# Connectors.net
KiCad netlist of a schematic drawn in Altium Designer
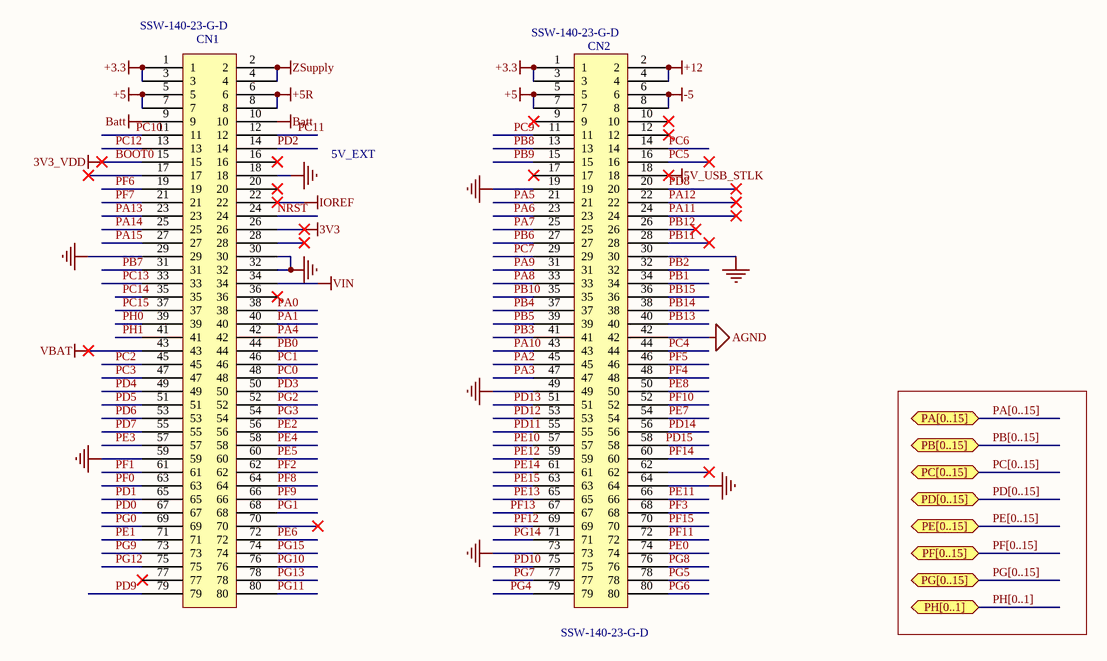
[diagram p0: Connectors.SchDoc]

(export (version "E")
  (design (tool "Eeschema 10.0.6"))
  (components
    (comp (ref "CN1")
      (value "SSW-140-23-G-D")
      (footprint "SSW-140-23-G-D")
      (description "80 Position Receptacle Connector Through Hole")
      (fields (field (name "SUPPLIER PART NUMBER 1") "SSW-140-23-G-D") (field (name "MANUFACTURER") "Samtec"))
      (libsource (lib "ZLS_Schematic_lib") (part "SSW-140-23-G-D"))
    )
    (comp (ref "CN2")
      (value "SSW-140-23-G-D")
      (footprint "SSW-140-23-G-D")
      (description "80 Position Receptacle Connector Through Hole")
      (fields (field (name "SUPPLIER PART NUMBER 1") "SSW-140-23-G-D") (field (name "MANUFACTURER") "Samtec"))
      (libsource (lib "ZLS_Schematic_lib") (part "SSW-140-23-G-D"))
    )
  )
  (nets
    (net (code "3") (name "+3.3") (class "Default")
      (node (ref "CN1") (pin "1") (pinfunction "1_1") (pintype "passive"))
      (node (ref "CN1") (pin "3") (pinfunction "3_3") (pintype "passive"))
      (node (ref "CN2") (pin "1") (pinfunction "1_1") (pintype "passive"))
      (node (ref "CN2") (pin "3") (pinfunction "3_3") (pintype "passive"))
    )
    (net (code "4") (name "+5") (class "Default")
      (node (ref "CN1") (pin "5") (pinfunction "5_5") (pintype "passive"))
      (node (ref "CN1") (pin "7") (pinfunction "7_7") (pintype "passive"))
      (node (ref "CN2") (pin "5") (pinfunction "5_5") (pintype "passive"))
      (node (ref "CN2") (pin "7") (pinfunction "7_7") (pintype "passive"))
    )
    (net (code "5") (name "+5R") (class "Default")
      (node (ref "CN1") (pin "6") (pinfunction "6_6") (pintype "passive"))
      (node (ref "CN1") (pin "8") (pinfunction "8_8") (pintype "passive"))
    )
    (net (code "6") (name "+12") (class "Default")
      (node (ref "CN2") (pin "2") (pinfunction "2_2") (pintype "passive"))
      (node (ref "CN2") (pin "4") (pinfunction "4_4") (pintype "passive"))
    )
    (net (code "7") (name "-5") (class "Default")
      (node (ref "CN2") (pin "6") (pinfunction "6_6") (pintype "passive"))
      (node (ref "CN2") (pin "8") (pinfunction "8_8") (pintype "passive"))
    )
    (net (code "8") (name "/NRST") (class "Default")
      (node (ref "CN1") (pin "24") (pinfunction "24_24") (pintype "passive"))
    )
    (net (code "9") (name "/PA0") (class "Default")
      (node (ref "CN1") (pin "38") (pinfunction "38_38") (pintype "passive"))
    )
    (net (code "10") (name "/PA1") (class "Default")
      (node (ref "CN1") (pin "40") (pinfunction "40_40") (pintype "passive"))
    )
    (net (code "11") (name "/PA2") (class "Default")
      (node (ref "CN2") (pin "45") (pinfunction "45_45") (pintype "passive"))
    )
    (net (code "12") (name "/PA3") (class "Default")
      (node (ref "CN2") (pin "47") (pinfunction "47_47") (pintype "passive"))
    )
    (net (code "13") (name "/PA4") (class "Default")
      (node (ref "CN1") (pin "42") (pinfunction "42_42") (pintype "passive"))
    )
    (net (code "14") (name "/PA5") (class "Default")
      (node (ref "CN2") (pin "21") (pinfunction "21_21") (pintype "passive"))
    )
    (net (code "15") (name "/PA6") (class "Default")
      (node (ref "CN2") (pin "23") (pinfunction "23_23") (pintype "passive"))
    )
    (net (code "16") (name "/PA7") (class "Default")
      (node (ref "CN2") (pin "25") (pinfunction "25_25") (pintype "passive"))
    )
    (net (code "17") (name "/PA8") (class "Default")
      (node (ref "CN2") (pin "33") (pinfunction "33_33") (pintype "passive"))
    )
    (net (code "18") (name "/PA9") (class "Default")
      (node (ref "CN2") (pin "31") (pinfunction "31_31") (pintype "passive"))
    )
    (net (code "19") (name "/PA10") (class "Default")
      (node (ref "CN2") (pin "43") (pinfunction "43_43") (pintype "passive"))
    )
    (net (code "20") (name "/PA11") (class "Default")
      (node (ref "CN2") (pin "24") (pinfunction "24_24") (pintype "passive+no_connect"))
    )
    (net (code "21") (name "/PA12") (class "Default")
      (node (ref "CN2") (pin "22") (pinfunction "22_22") (pintype "passive+no_connect"))
    )
    (net (code "22") (name "/PA13") (class "Default")
      (node (ref "CN1") (pin "23") (pinfunction "23_23") (pintype "passive"))
    )
    (net (code "23") (name "/PA14") (class "Default")
      (node (ref "CN1") (pin "25") (pinfunction "25_25") (pintype "passive"))
    )
    (net (code "24") (name "/PA15") (class "Default")
      (node (ref "CN1") (pin "27") (pinfunction "27_27") (pintype "passive"))
    )
    (net (code "26") (name "/PB0") (class "Default")
      (node (ref "CN1") (pin "44") (pinfunction "44_44") (pintype "passive"))
    )
    (net (code "27") (name "/PB1") (class "Default")
      (node (ref "CN2") (pin "34") (pinfunction "34_34") (pintype "passive"))
    )
    (net (code "28") (name "/PB2") (class "Default")
      (node (ref "CN2") (pin "32") (pinfunction "32_32") (pintype "passive"))
    )
    (net (code "29") (name "/PB3") (class "Default")
      (node (ref "CN2") (pin "41") (pinfunction "41_41") (pintype "passive"))
    )
    (net (code "30") (name "/PB4") (class "Default")
      (node (ref "CN2") (pin "37") (pinfunction "37_37") (pintype "passive"))
    )
    (net (code "31") (name "/PB5") (class "Default")
      (node (ref "CN2") (pin "39") (pinfunction "39_39") (pintype "passive"))
    )
    (net (code "32") (name "/PB6") (class "Default")
      (node (ref "CN2") (pin "27") (pinfunction "27_27") (pintype "passive"))
    )
    (net (code "33") (name "/PB7") (class "Default")
      (node (ref "CN1") (pin "31") (pinfunction "31_31") (pintype "passive"))
    )
    (net (code "34") (name "/PB8") (class "Default")
      (node (ref "CN2") (pin "13") (pinfunction "13_13") (pintype "passive"))
    )
    (net (code "35") (name "/PB9") (class "Default")
      (node (ref "CN2") (pin "15") (pinfunction "15_15") (pintype "passive"))
    )
    (net (code "36") (name "/PB10") (class "Default")
      (node (ref "CN2") (pin "35") (pinfunction "35_35") (pintype "passive"))
    )
    (net (code "37") (name "/PB11") (class "Default")
      (node (ref "CN2") (pin "28") (pinfunction "28_28") (pintype "passive+no_connect"))
    )
    (net (code "38") (name "/PB12") (class "Default")
      (node (ref "CN2") (pin "26") (pinfunction "26_26") (pintype "passive+no_connect"))
    )
    (net (code "39") (name "/PB13") (class "Default")
      (node (ref "CN2") (pin "40") (pinfunction "40_40") (pintype "passive"))
    )
    (net (code "40") (name "/PB14") (class "Default")
      (node (ref "CN2") (pin "38") (pinfunction "38_38") (pintype "passive"))
    )
    (net (code "41") (name "/PB15") (class "Default")
      (node (ref "CN2") (pin "36") (pinfunction "36_36") (pintype "passive"))
    )
    (net (code "43") (name "/PC0") (class "Default")
      (node (ref "CN1") (pin "48") (pinfunction "48_48") (pintype "passive"))
    )
    (net (code "44") (name "/PC1") (class "Default")
      (node (ref "CN1") (pin "46") (pinfunction "46_46") (pintype "passive"))
    )
    (net (code "45") (name "/PC2") (class "Default")
      (node (ref "CN1") (pin "45") (pinfunction "45_45") (pintype "passive"))
    )
    (net (code "46") (name "/PC3") (class "Default")
      (node (ref "CN1") (pin "47") (pinfunction "47_47") (pintype "passive"))
    )
    (net (code "47") (name "/PC4") (class "Default")
      (node (ref "CN2") (pin "44") (pinfunction "44_44") (pintype "passive"))
    )
    (net (code "48") (name "/PC5") (class "Default")
      (node (ref "CN2") (pin "16") (pinfunction "16_16") (pintype "passive+no_connect"))
    )
    (net (code "49") (name "/PC6") (class "Default")
      (node (ref "CN2") (pin "14") (pinfunction "14_14") (pintype "passive"))
    )
    (net (code "50") (name "/PC7") (class "Default")
      (node (ref "CN2") (pin "29") (pinfunction "29_29") (pintype "passive"))
    )
    (net (code "51") (name "/PC9") (class "Default")
      (node (ref "CN2") (pin "11") (pinfunction "11_11") (pintype "passive"))
    )
    (net (code "52") (name "/PC10") (class "Default")
      (node (ref "CN1") (pin "11") (pinfunction "11_11") (pintype "passive"))
    )
    (net (code "53") (name "/PC11") (class "Default")
      (node (ref "CN1") (pin "12") (pinfunction "12_12") (pintype "passive"))
    )
    (net (code "54") (name "/PC12") (class "Default")
      (node (ref "CN1") (pin "13") (pinfunction "13_13") (pintype "passive"))
    )
    (net (code "55") (name "/PC13") (class "Default")
      (node (ref "CN1") (pin "33") (pinfunction "33_33") (pintype "passive"))
    )
    (net (code "56") (name "/PC14") (class "Default")
      (node (ref "CN1") (pin "35") (pinfunction "35_35") (pintype "passive"))
    )
    (net (code "57") (name "/PC15") (class "Default")
      (node (ref "CN1") (pin "37") (pinfunction "37_37") (pintype "passive"))
    )
    (net (code "59") (name "/PD0") (class "Default")
      (node (ref "CN1") (pin "67") (pinfunction "67_67") (pintype "passive"))
    )
    (net (code "60") (name "/PD1") (class "Default")
      (node (ref "CN1") (pin "65") (pinfunction "65_65") (pintype "passive"))
    )
    (net (code "61") (name "/PD2") (class "Default")
      (node (ref "CN1") (pin "14") (pinfunction "14_14") (pintype "passive"))
    )
    (net (code "62") (name "/PD3") (class "Default")
      (node (ref "CN1") (pin "50") (pinfunction "50_50") (pintype "passive"))
    )
    (net (code "63") (name "/PD4") (class "Default")
      (node (ref "CN1") (pin "49") (pinfunction "49_49") (pintype "passive"))
    )
    (net (code "64") (name "/PD5") (class "Default")
      (node (ref "CN1") (pin "51") (pinfunction "51_51") (pintype "passive"))
    )
    (net (code "65") (name "/PD6") (class "Default")
      (node (ref "CN1") (pin "53") (pinfunction "53_53") (pintype "passive"))
    )
    (net (code "66") (name "/PD7") (class "Default")
      (node (ref "CN1") (pin "55") (pinfunction "55_55") (pintype "passive"))
    )
    (net (code "67") (name "/PD8") (class "Default")
      (node (ref "CN2") (pin "20") (pinfunction "20_20") (pintype "passive+no_connect"))
    )
    (net (code "68") (name "/PD9") (class "Default")
      (node (ref "CN1") (pin "79") (pinfunction "79_79") (pintype "passive"))
    )
    (net (code "69") (name "/PD10") (class "Default")
      (node (ref "CN2") (pin "75") (pinfunction "75_75") (pintype "passive"))
    )
    (net (code "70") (name "/PD11") (class "Default")
      (node (ref "CN2") (pin "55") (pinfunction "55_55") (pintype "passive"))
    )
    (net (code "71") (name "/PD12") (class "Default")
      (node (ref "CN2") (pin "53") (pinfunction "53_53") (pintype "passive"))
    )
    (net (code "72") (name "/PD13") (class "Default")
      (node (ref "CN2") (pin "51") (pinfunction "51_51") (pintype "passive"))
    )
    (net (code "73") (name "/PD14") (class "Default")
      (node (ref "CN2") (pin "56") (pinfunction "56_56") (pintype "passive"))
    )
    (net (code "76") (name "/PE0") (class "Default")
      (node (ref "CN2") (pin "74") (pinfunction "74_74") (pintype "passive"))
    )
    (net (code "77") (name "/PE1") (class "Default")
      (node (ref "CN1") (pin "71") (pinfunction "71_71") (pintype "passive"))
    )
    (net (code "78") (name "/PE2") (class "Default")
      (node (ref "CN1") (pin "56") (pinfunction "56_56") (pintype "passive"))
    )
    (net (code "79") (name "/PE3") (class "Default")
      (node (ref "CN1") (pin "57") (pinfunction "57_57") (pintype "passive"))
    )
    (net (code "80") (name "/PE4") (class "Default")
      (node (ref "CN1") (pin "58") (pinfunction "58_58") (pintype "passive"))
    )
    (net (code "81") (name "/PE5") (class "Default")
      (node (ref "CN1") (pin "60") (pinfunction "60_60") (pintype "passive"))
    )
    (net (code "82") (name "/PE6") (class "Default")
      (node (ref "CN1") (pin "72") (pinfunction "72_72") (pintype "passive"))
    )
    (net (code "83") (name "/PE7") (class "Default")
      (node (ref "CN2") (pin "54") (pinfunction "54_54") (pintype "passive"))
    )
    (net (code "84") (name "/PE8") (class "Default")
      (node (ref "CN2") (pin "50") (pinfunction "50_50") (pintype "passive"))
    )
    (net (code "85") (name "/PE10") (class "Default")
      (node (ref "CN2") (pin "57") (pinfunction "57_57") (pintype "passive"))
    )
    (net (code "86") (name "/PE11") (class "Default")
      (node (ref "CN2") (pin "66") (pinfunction "66_66") (pintype "passive"))
    )
    (net (code "87") (name "/PE12") (class "Default")
      (node (ref "CN2") (pin "59") (pinfunction "59_59") (pintype "passive"))
    )
    (net (code "88") (name "/PE13") (class "Default")
      (node (ref "CN2") (pin "65") (pinfunction "65_65") (pintype "passive"))
    )
    (net (code "89") (name "/PE14") (class "Default")
      (node (ref "CN2") (pin "61") (pinfunction "61_61") (pintype "passive"))
    )
    (net (code "90") (name "/PE15") (class "Default")
      (node (ref "CN2") (pin "63") (pinfunction "63_63") (pintype "passive"))
    )
    (net (code "92") (name "/PF0") (class "Default")
      (node (ref "CN1") (pin "63") (pinfunction "63_63") (pintype "passive"))
    )
    (net (code "93") (name "/PF1") (class "Default")
      (node (ref "CN1") (pin "61") (pinfunction "61_61") (pintype "passive"))
    )
    (net (code "94") (name "/PF2") (class "Default")
      (node (ref "CN1") (pin "62") (pinfunction "62_62") (pintype "passive"))
    )
    (net (code "95") (name "/PF3") (class "Default")
      (node (ref "CN2") (pin "68") (pinfunction "68_68") (pintype "passive"))
    )
    (net (code "96") (name "/PF4") (class "Default")
      (node (ref "CN2") (pin "48") (pinfunction "48_48") (pintype "passive"))
    )
    (net (code "97") (name "/PF5") (class "Default")
      (node (ref "CN2") (pin "46") (pinfunction "46_46") (pintype "passive"))
    )
    (net (code "98") (name "/PF6") (class "Default")
      (node (ref "CN1") (pin "19") (pinfunction "19_19") (pintype "passive"))
    )
    (net (code "99") (name "/PF7") (class "Default")
      (node (ref "CN1") (pin "21") (pinfunction "21_21") (pintype "passive"))
    )
    (net (code "100") (name "/PF8") (class "Default")
      (node (ref "CN1") (pin "64") (pinfunction "64_64") (pintype "passive"))
    )
    (net (code "101") (name "/PF9") (class "Default")
      (node (ref "CN1") (pin "66") (pinfunction "66_66") (pintype "passive"))
    )
    (net (code "102") (name "/PF10") (class "Default")
      (node (ref "CN2") (pin "52") (pinfunction "52_52") (pintype "passive"))
    )
    (net (code "103") (name "/PF11") (class "Default")
      (node (ref "CN2") (pin "72") (pinfunction "72_72") (pintype "passive"))
    )
    (net (code "104") (name "/PF12") (class "Default")
      (node (ref "CN2") (pin "69") (pinfunction "69_69") (pintype "passive"))
    )
    (net (code "105") (name "/PF13") (class "Default")
      (node (ref "CN2") (pin "67") (pinfunction "67_67") (pintype "passive"))
    )
    (net (code "106") (name "/PF14") (class "Default")
      (node (ref "CN2") (pin "60") (pinfunction "60_60") (pintype "passive"))
    )
    (net (code "107") (name "/PF15") (class "Default")
      (node (ref "CN2") (pin "70") (pinfunction "70_70") (pintype "passive"))
    )
    (net (code "109") (name "/PG0") (class "Default")
      (node (ref "CN1") (pin "69") (pinfunction "69_69") (pintype "passive"))
    )
    (net (code "110") (name "/PG1") (class "Default")
      (node (ref "CN1") (pin "68") (pinfunction "68_68") (pintype "passive"))
    )
    (net (code "111") (name "/PG2") (class "Default")
      (node (ref "CN1") (pin "52") (pinfunction "52_52") (pintype "passive"))
    )
    (net (code "112") (name "/PG3") (class "Default")
      (node (ref "CN1") (pin "54") (pinfunction "54_54") (pintype "passive"))
    )
    (net (code "113") (name "/PG4") (class "Default")
      (node (ref "CN2") (pin "79") (pinfunction "79_79") (pintype "passive"))
    )
    (net (code "114") (name "/PG5") (class "Default")
      (node (ref "CN2") (pin "78") (pinfunction "78_78") (pintype "passive"))
    )
    (net (code "115") (name "/PG6") (class "Default")
      (node (ref "CN2") (pin "80") (pinfunction "80_80") (pintype "passive"))
    )
    (net (code "116") (name "/PG7") (class "Default")
      (node (ref "CN2") (pin "77") (pinfunction "77_77") (pintype "passive"))
    )
    (net (code "117") (name "/PG8") (class "Default")
      (node (ref "CN2") (pin "76") (pinfunction "76_76") (pintype "passive"))
    )
    (net (code "118") (name "/PG9") (class "Default")
      (node (ref "CN1") (pin "73") (pinfunction "73_73") (pintype "passive"))
    )
    (net (code "119") (name "/PG10") (class "Default")
      (node (ref "CN1") (pin "76") (pinfunction "76_76") (pintype "passive"))
    )
    (net (code "120") (name "/PG11") (class "Default")
      (node (ref "CN1") (pin "80") (pinfunction "80_80") (pintype "passive"))
    )
    (net (code "121") (name "/PG12") (class "Default")
      (node (ref "CN1") (pin "75") (pinfunction "75_75") (pintype "passive"))
    )
    (net (code "122") (name "/PG13") (class "Default")
      (node (ref "CN1") (pin "78") (pinfunction "78_78") (pintype "passive"))
    )
    (net (code "123") (name "/PG14") (class "Default")
      (node (ref "CN2") (pin "71") (pinfunction "71_71") (pintype "passive"))
    )
    (net (code "124") (name "/PG15") (class "Default")
      (node (ref "CN1") (pin "74") (pinfunction "74_74") (pintype "passive"))
    )
    (net (code "126") (name "/PH0") (class "Default")
      (node (ref "CN1") (pin "39") (pinfunction "39_39") (pintype "passive"))
    )
    (net (code "127") (name "/PH1") (class "Default")
      (node (ref "CN1") (pin "41") (pinfunction "41_41") (pintype "passive"))
    )
    (net (code "129") (name "3V3") (class "Default")
      (node (ref "CN1") (pin "26") (pinfunction "26_26") (pintype "passive"))
    )
    (net (code "130") (name "3V3_VDD") (class "Default")
      (node (ref "CN1") (pin "15") (pinfunction "15_15") (pintype "passive"))
    )
    (net (code "131") (name "5V_USB_STLK") (class "Default")
      (node (ref "CN2") (pin "18") (pinfunction "18_18") (pintype "passive"))
    )
    (net (code "132") (name "AGND") (class "Default")
      (node (ref "CN2") (pin "42") (pinfunction "42_42") (pintype "passive"))
    )
    (net (code "133") (name "Batt") (class "Default")
      (node (ref "CN1") (pin "10") (pinfunction "10_10") (pintype "passive"))
      (node (ref "CN1") (pin "9") (pinfunction "9_9") (pintype "passive"))
    )
    (net (code "134") (name "GND") (class "Default")
      (node (ref "CN1") (pin "18") (pinfunction "18_18") (pintype "passive"))
      (node (ref "CN1") (pin "29") (pinfunction "29_29") (pintype "passive"))
      (node (ref "CN1") (pin "30") (pinfunction "30_30") (pintype "passive"))
      (node (ref "CN1") (pin "32") (pinfunction "32_32") (pintype "passive"))
      (node (ref "CN1") (pin "59") (pinfunction "59_59") (pintype "passive"))
      (node (ref "CN2") (pin "19") (pinfunction "19_19") (pintype "passive"))
      (node (ref "CN2") (pin "30") (pinfunction "30_30") (pintype "passive"))
      (node (ref "CN2") (pin "49") (pinfunction "49_49") (pintype "passive"))
      (node (ref "CN2") (pin "64") (pinfunction "64_64") (pintype "passive"))
      (node (ref "CN2") (pin "73") (pinfunction "73_73") (pintype "passive"))
    )
    (net (code "135") (name "IOREF") (class "Default")
      (node (ref "CN1") (pin "22") (pinfunction "22_22") (pintype "passive"))
    )
    (net (code "136") (name "VBAT") (class "Default")
      (node (ref "CN1") (pin "43") (pinfunction "43_43") (pintype "passive"))
    )
    (net (code "137") (name "VIN") (class "Default")
      (node (ref "CN1") (pin "34") (pinfunction "34_34") (pintype "passive"))
    )
    (net (code "138") (name "ZSupply") (class "Default")
      (node (ref "CN1") (pin "2") (pinfunction "2_2") (pintype "passive"))
      (node (ref "CN1") (pin "4") (pinfunction "4_4") (pintype "passive"))
    )
    (net (code "139") (name "unconnected-(CN1-Pad16)") (class "Default")
      (node (ref "CN1") (pin "16") (pinfunction "16_16") (pintype "passive+no_connect"))
    )
    (net (code "140") (name "unconnected-(CN1-Pad17)") (class "Default")
      (node (ref "CN1") (pin "17") (pinfunction "17_17") (pintype "passive+no_connect"))
    )
    (net (code "141") (name "unconnected-(CN1-Pad20)") (class "Default")
      (node (ref "CN1") (pin "20") (pinfunction "20_20") (pintype "passive+no_connect"))
    )
    (net (code "142") (name "unconnected-(CN1-Pad28)") (class "Default")
      (node (ref "CN1") (pin "28") (pinfunction "28_28") (pintype "passive+no_connect"))
    )
    (net (code "143") (name "unconnected-(CN1-Pad36)") (class "Default")
      (node (ref "CN1") (pin "36") (pinfunction "36_36") (pintype "passive+no_connect"))
    )
    (net (code "144") (name "unconnected-(CN1-Pad70)") (class "Default")
      (node (ref "CN1") (pin "70") (pinfunction "70_70") (pintype "passive+no_connect"))
    )
    (net (code "145") (name "unconnected-(CN1-Pad77)") (class "Default")
      (node (ref "CN1") (pin "77") (pinfunction "77_77") (pintype "passive+no_connect"))
    )
    (net (code "146") (name "unconnected-(CN2-Pad9)") (class "Default")
      (node (ref "CN2") (pin "9") (pinfunction "9_9") (pintype "passive+no_connect"))
    )
    (net (code "147") (name "unconnected-(CN2-Pad10)") (class "Default")
      (node (ref "CN2") (pin "10") (pinfunction "10_10") (pintype "passive+no_connect"))
    )
    (net (code "148") (name "unconnected-(CN2-Pad12)") (class "Default")
      (node (ref "CN2") (pin "12") (pinfunction "12_12") (pintype "passive+no_connect"))
    )
    (net (code "149") (name "unconnected-(CN2-Pad17)") (class "Default")
      (node (ref "CN2") (pin "17") (pinfunction "17_17") (pintype "passive+no_connect"))
    )
    (net (code "150") (name "unconnected-(CN2-Pad58)") (class "Default")
      (node (ref "CN2") (pin "58") (pinfunction "58_58") (pintype "passive"))
    )
    (net (code "151") (name "unconnected-(CN2-Pad62)") (class "Default")
      (node (ref "CN2") (pin "62") (pinfunction "62_62") (pintype "passive+no_connect"))
    )
  )
)
